# electric-imp-breakout.net
KiCad netlist of a schematic drawn in EAGLE
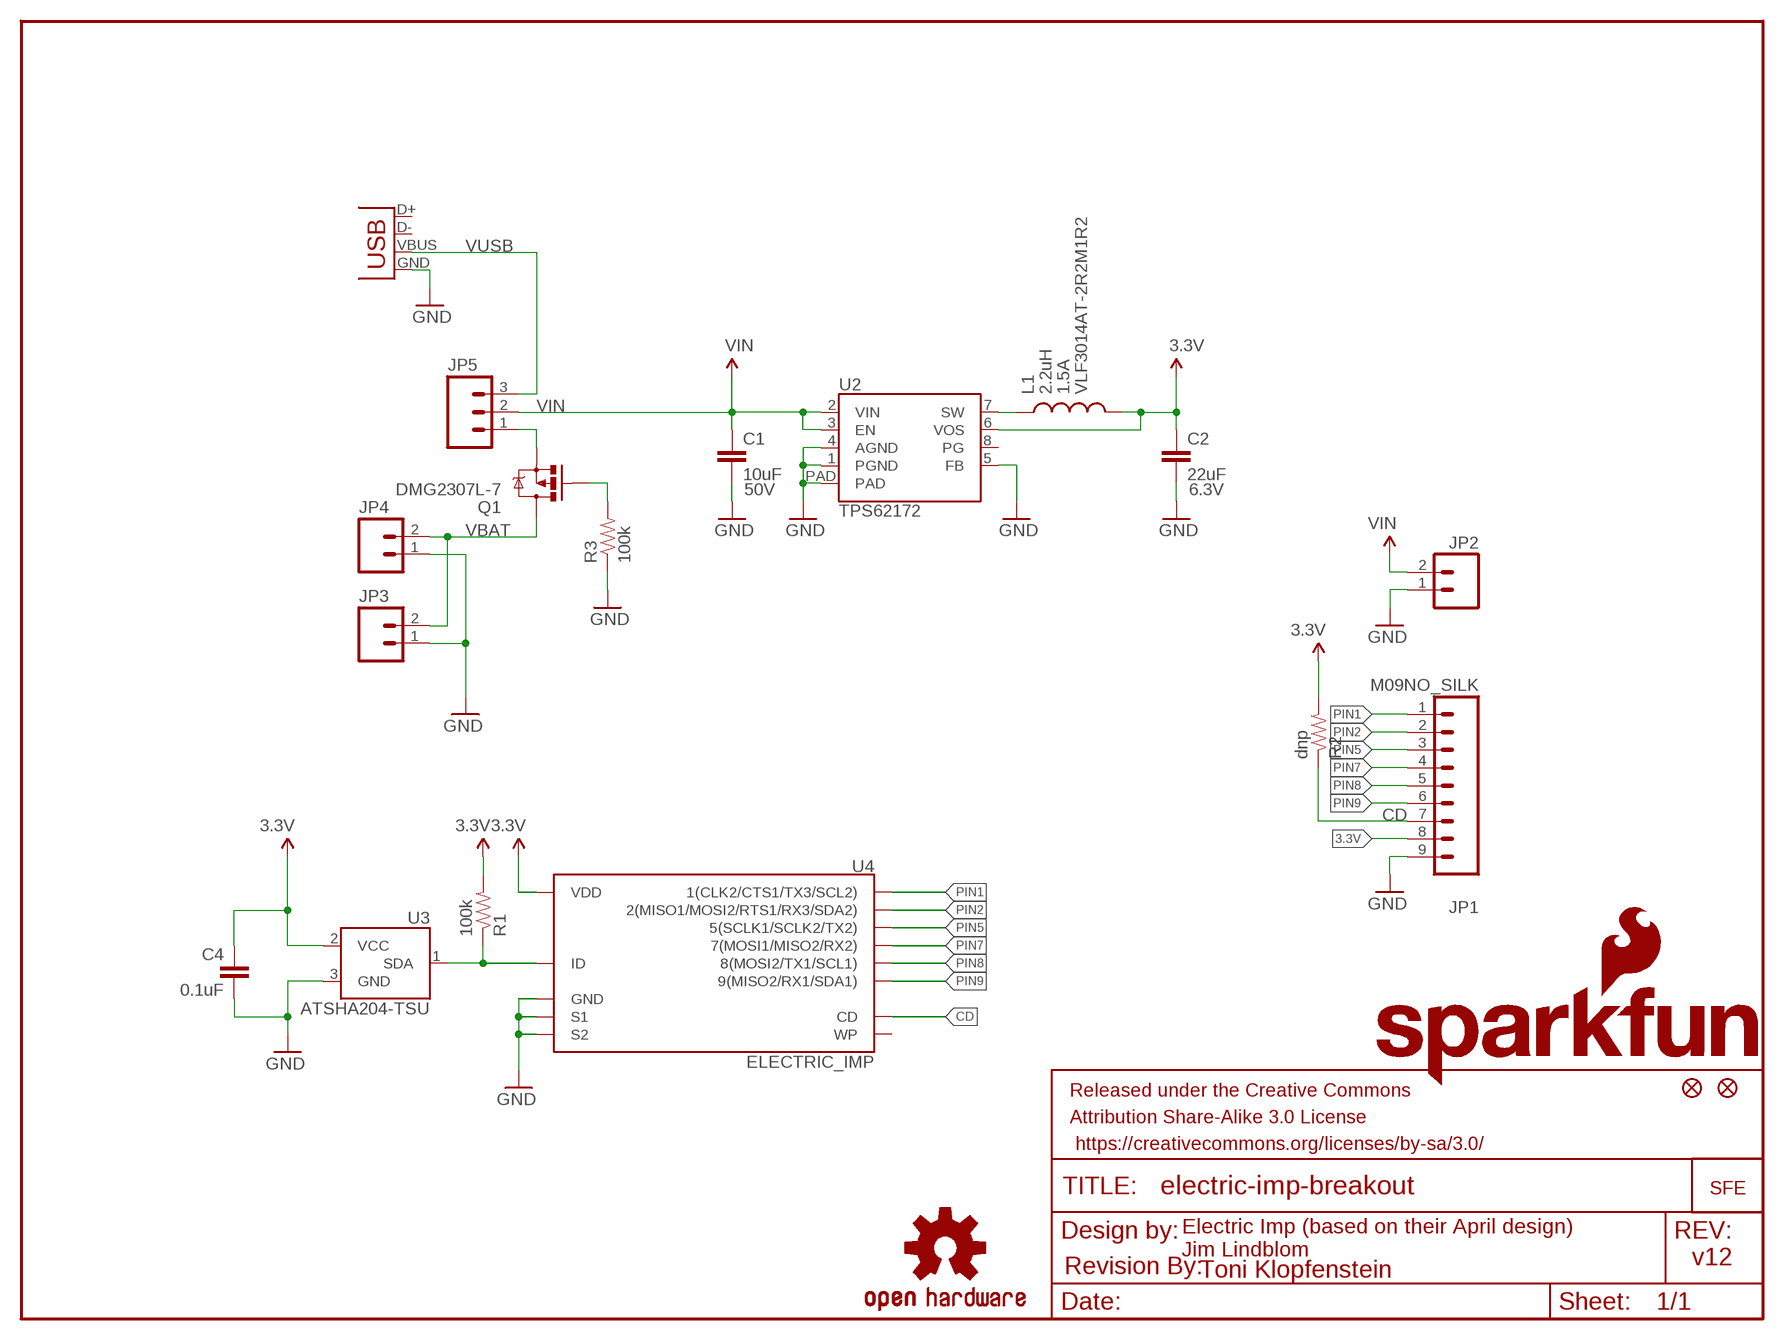
[diagram p0: schematic, sheet 1]

(export (version "E")
  (design (tool "Eeschema 10.0.6"))
  (components
    (comp (ref "C1")
      (value "10uF")
      (footprint "eagle-import:1210")
      (libsource (lib "eagle-import") (part "10UF50V20%(1210)"))
    )
    (comp (ref "C2")
      (value "22uF")
      (footprint "eagle-import:0805")
      (libsource (lib "eagle-import") (part "22UF-6.3V-20%(0805)"))
    )
    (comp (ref "C4")
      (value "0.1uF")
      (footprint "eagle-import:0603-CAP")
      (libsource (lib "eagle-import") (part "0.1UF-25V(+80/-20%)(0603)"))
    )
    (comp (ref "FID1")
      (value "FIDUCIAL1X2")
      (footprint "eagle-import:FIDUCIAL-1X2")
      (libsource (lib "eagle-import") (part "FIDUCIAL1X2"))
    )
    (comp (ref "FID2")
      (value "FIDUCIAL1X2")
      (footprint "eagle-import:FIDUCIAL-1X2")
      (libsource (lib "eagle-import") (part "FIDUCIAL1X2"))
    )
    (comp (ref "FRAME1")
      (value "FRAME-LETTER")
      (footprint "eagle-import:CREATIVE_COMMONS")
      (libsource (lib "eagle-import") (part "FRAME-LETTER"))
    )
    (comp (ref "JP1")
      (value "M09NO_SILK")
      (footprint "eagle-import:1X09_NO_SILK")
      (libsource (lib "eagle-import") (part "M09NO_SILK"))
    )
    (comp (ref "JP2")
      (value "M021X02_NO_SILK")
      (footprint "eagle-import:1X02_NO_SILK")
      (libsource (lib "eagle-import") (part "M021X02_NO_SILK"))
    )
    (comp (ref "JP3")
      (value "M02SMD")
      (footprint "eagle-import:1X02_SMD")
      (libsource (lib "eagle-import") (part "M02SMD"))
    )
    (comp (ref "JP4")
      (value "M02-JST-2-PTH-NO_SILK")
      (footprint "eagle-import:JST-2-PTH-NS")
      (libsource (lib "eagle-import") (part "M02-JST-2-PTH-NO_SILK"))
    )
    (comp (ref "JP5")
      (value "M031X03_NO_SILK")
      (footprint "eagle-import:1X03_NO_SILK")
      (libsource (lib "eagle-import") (part "M031X03_NO_SILK"))
    )
    (comp (ref "JP6")
      (value "LOGO-SFESK")
      (footprint "eagle-import:SFE-LOGO-FLAME")
      (libsource (lib "eagle-import") (part "LOGO-SFESK"))
    )
    (comp (ref "JP7")
      (value "SFE_LOGO_NAME_FLAME.1_INCH")
      (footprint "eagle-import:SFE_LOGO_NAME_FLAME_.1")
      (libsource (lib "eagle-import") (part "SFE_LOGO_NAME_FLAME.1_INCH"))
    )
    (comp (ref "L1")
      (value "2.2uH")
      (footprint "eagle-import:VLF4012A")
      (libsource (lib "eagle-import") (part "INDUCTORVLF4012A"))
    )
    (comp (ref "Q1")
      (value "DMG2307L-7")
      (footprint "eagle-import:SOT23-3")
      (libsource (lib "eagle-import") (part "MOSFET-PCHANNELSMD"))
    )
    (comp (ref "R1")
      (value "100k")
      (footprint "eagle-import:0603-RES")
      (libsource (lib "eagle-import") (part "100KOHM1/10W1%(0603)"))
    )
    (comp (ref "R2")
      (value "dnp")
      (footprint "eagle-import:0603-RES")
      (libsource (lib "eagle-import") (part "RESISTOR0603"))
    )
    (comp (ref "R3")
      (value "100k")
      (footprint "eagle-import:0603-RES")
      (libsource (lib "eagle-import") (part "100KOHM1/10W1%(0603)"))
    )
    (comp (ref "U$3")
      (value "REVISION")
      (footprint "eagle-import:REVISION")
      (libsource (lib "eagle-import") (part "REVISION"))
    )
    (comp (ref "U$5")
      (value "OSHW-LOGOS")
      (footprint "eagle-import:OSHW-LOGO-S")
      (libsource (lib "eagle-import") (part "OSHW-LOGOS"))
    )
    (comp (ref "U2")
      (value "TPS62172")
      (footprint "eagle-import:WSON-8-PAD")
      (libsource (lib "eagle-import") (part "TPS62172"))
    )
    (comp (ref "U3")
      (value "ATSHA204-TSU")
      (footprint "eagle-import:SOT23-3")
      (libsource (lib "eagle-import") (part "ATSHA204-TSU"))
    )
    (comp (ref "U4")
      (value "ELECTRIC_IMP")
      (footprint "eagle-import:SD_1_1")
      (libsource (lib "eagle-import") (part "ELECTRIC_IMP"))
    )
    (comp (ref "X1")
      (value "USBSMD")
      (footprint "eagle-import:USB-MINIB")
      (libsource (lib "eagle-import") (part "USBSMD"))
    )
  )
  (nets
    (net (code "1") (name "/VBAT") (class "Default")
      (node (ref "JP3") (pin "2") (pinfunction "2_2") (pintype "passive"))
      (node (ref "JP4") (pin "2") (pinfunction "2_2") (pintype "passive"))
      (node (ref "Q1") (pin "3") (pinfunction "D_3") (pintype "passive"))
    )
    (net (code "2") (name "/VUSB") (class "Default")
      (node (ref "JP5") (pin "3") (pinfunction "3_3") (pintype "passive"))
      (node (ref "X1") (pin "VBUS") (pinfunction "VBUS_VBUS") (pintype "bidirectional"))
    )
    (net (code "3") (name "3.3V") (class "Default")
      (node (ref "C2") (pin "1") (pinfunction "1_1") (pintype "passive"))
      (node (ref "C4") (pin "1") (pinfunction "1_1") (pintype "passive"))
      (node (ref "JP1") (pin "8") (pinfunction "8_8") (pintype "passive"))
      (node (ref "L1") (pin "P$2") (pinfunction "2_P$2") (pintype "passive"))
      (node (ref "R1") (pin "2") (pinfunction "2_2") (pintype "passive"))
      (node (ref "R2") (pin "2") (pinfunction "2_2") (pintype "passive"))
      (node (ref "U2") (pin "6") (pinfunction "VOS_6") (pintype "bidirectional"))
      (node (ref "U3") (pin "2") (pinfunction "VCC_2") (pintype "bidirectional"))
      (node (ref "U4") (pin "4") (pinfunction "VDD_4") (pintype "bidirectional"))
    )
    (net (code "4") (name "CD") (class "Default")
      (node (ref "JP1") (pin "7") (pinfunction "7_7") (pintype "passive"))
      (node (ref "R2") (pin "1") (pinfunction "1_1") (pintype "passive"))
      (node (ref "U4") (pin "CD") (pinfunction "CD_CD") (pintype "bidirectional"))
    )
    (net (code "5") (name "GND") (class "Default")
      (node (ref "C1") (pin "2") (pinfunction "2_2") (pintype "passive"))
      (node (ref "C2") (pin "2") (pinfunction "2_2") (pintype "passive"))
      (node (ref "C4") (pin "2") (pinfunction "2_2") (pintype "passive"))
      (node (ref "JP1") (pin "9") (pinfunction "9_9") (pintype "passive"))
      (node (ref "JP2") (pin "1") (pinfunction "1_1") (pintype "passive"))
      (node (ref "JP3") (pin "1") (pinfunction "1_1") (pintype "passive"))
      (node (ref "JP4") (pin "1") (pinfunction "1_1") (pintype "passive"))
      (node (ref "R3") (pin "1") (pinfunction "1_1") (pintype "passive"))
      (node (ref "U2") (pin "1") (pinfunction "PGND_1") (pintype "bidirectional"))
      (node (ref "U2") (pin "4") (pinfunction "AGND_4") (pintype "bidirectional"))
      (node (ref "U2") (pin "5") (pinfunction "FB_5") (pintype "bidirectional"))
      (node (ref "U2") (pin "PAD") (pinfunction "PAD_PAD") (pintype "bidirectional"))
      (node (ref "U3") (pin "3") (pinfunction "GND_3") (pintype "bidirectional"))
      (node (ref "U4") (pin "3") (pinfunction "GND_3") (pintype "bidirectional"))
      (node (ref "U4") (pin "SH@1") (pinfunction "S1_SH@1") (pintype "bidirectional"))
      (node (ref "U4") (pin "SH@2") (pinfunction "S2_SH@2") (pintype "bidirectional"))
      (node (ref "X1") (pin "GND") (pinfunction "GND_GND") (pintype "bidirectional"))
    )
    (net (code "6") (name "Net-(L1-1)") (class "Default")
      (node (ref "L1") (pin "P$1") (pinfunction "1_P$1") (pintype "passive"))
      (node (ref "U2") (pin "7") (pinfunction "SW_7") (pintype "bidirectional"))
    )
    (net (code "7") (name "Net-(Q1-G)") (class "Default")
      (node (ref "Q1") (pin "1") (pinfunction "G_1") (pintype "passive"))
      (node (ref "R3") (pin "2") (pinfunction "2_2") (pintype "passive"))
    )
    (net (code "8") (name "Net-(Q1-S)") (class "Default")
      (node (ref "JP5") (pin "1") (pinfunction "1_1") (pintype "passive"))
      (node (ref "Q1") (pin "2") (pinfunction "S_2") (pintype "passive"))
    )
    (net (code "9") (name "Net-(U3-SDA)") (class "Default")
      (node (ref "R1") (pin "1") (pinfunction "1_1") (pintype "passive"))
      (node (ref "U3") (pin "1") (pinfunction "SDA_1") (pintype "bidirectional"))
      (node (ref "U4") (pin "6") (pinfunction "ID_6") (pintype "bidirectional"))
    )
    (net (code "10") (name "PIN1") (class "Default")
      (node (ref "JP1") (pin "1") (pinfunction "1_1") (pintype "passive"))
      (node (ref "U4") (pin "1") (pinfunction "1(CLK2/CTS1/TX3/SCL2)_1") (pintype "bidirectional"))
    )
    (net (code "11") (name "PIN2") (class "Default")
      (node (ref "JP1") (pin "2") (pinfunction "2_2") (pintype "passive"))
      (node (ref "U4") (pin "2") (pinfunction "2(MISO1/MOSI2/RTS1/RX3/SDA2)_2") (pintype "bidirectional"))
    )
    (net (code "12") (name "PIN5") (class "Default")
      (node (ref "JP1") (pin "3") (pinfunction "3_3") (pintype "passive"))
      (node (ref "U4") (pin "5") (pinfunction "5(SCLK1/SCLK2/TX2)_5") (pintype "bidirectional"))
    )
    (net (code "13") (name "PIN7") (class "Default")
      (node (ref "JP1") (pin "4") (pinfunction "4_4") (pintype "passive"))
      (node (ref "U4") (pin "7") (pinfunction "7(MOSI1/MISO2/RX2)_7") (pintype "bidirectional"))
    )
    (net (code "14") (name "PIN8") (class "Default")
      (node (ref "JP1") (pin "5") (pinfunction "5_5") (pintype "passive"))
      (node (ref "U4") (pin "8") (pinfunction "8(MOSI2/TX1/SCL1)_8") (pintype "bidirectional"))
    )
    (net (code "15") (name "PIN9") (class "Default")
      (node (ref "JP1") (pin "6") (pinfunction "6_6") (pintype "passive"))
      (node (ref "U4") (pin "9") (pinfunction "9(MISO2/RX1/SDA1)_9") (pintype "bidirectional"))
    )
    (net (code "16") (name "VIN") (class "Default")
      (node (ref "C1") (pin "1") (pinfunction "1_1") (pintype "passive"))
      (node (ref "JP2") (pin "2") (pinfunction "2_2") (pintype "passive"))
      (node (ref "JP5") (pin "2") (pinfunction "2_2") (pintype "passive"))
      (node (ref "U2") (pin "2") (pinfunction "VIN_2") (pintype "bidirectional"))
      (node (ref "U2") (pin "3") (pinfunction "EN_3") (pintype "bidirectional"))
    )
    (net (code "17") (name "unconnected-(U2-PG-Pad8)") (class "Default")
      (node (ref "U2") (pin "8") (pinfunction "PG_8") (pintype "bidirectional"))
    )
    (net (code "18") (name "unconnected-(U4-PadWP)") (class "Default")
      (node (ref "U4") (pin "WP") (pinfunction "WP_WP") (pintype "bidirectional"))
    )
    (net (code "19") (name "unconnected-(X1-PadD+)") (class "Default")
      (node (ref "X1") (pin "D+") (pinfunction "D+_D+") (pintype "bidirectional"))
    )
    (net (code "20") (name "unconnected-(X1-PadD-)") (class "Default")
      (node (ref "X1") (pin "D-") (pinfunction "D-_D-") (pintype "bidirectional"))
    )
  )
)
